# Mynd_Baffle.net
KiCad netlist of a schematic drawn in Altium Designer
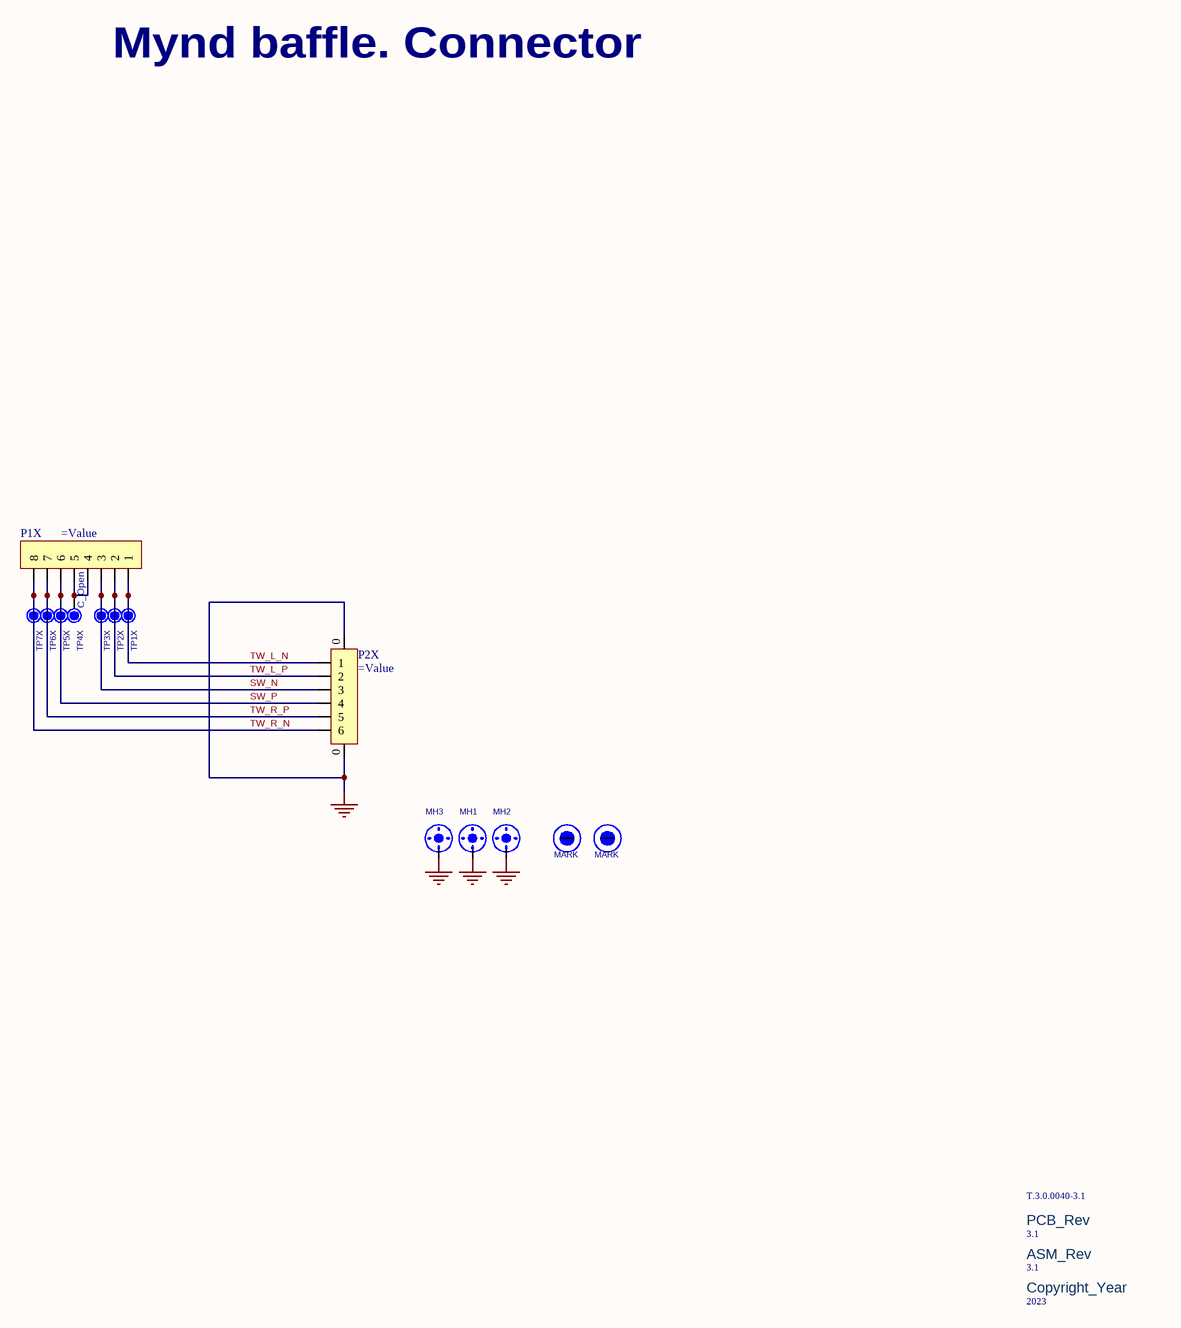
[diagram p0: Mynd_Baffle.SchDoc]

(export (version "E")
  (design (tool "Eeschema 10.0.6"))
  (components
    (comp (ref "MH1")
      (value "SCREW_HOLE_D35")
      (footprint "SCREW_D35")
      (description "SCREW_HOLE D3.5mm")
      (libsource (lib "altium-import") (part "root_1_SCREW_HOLE_"))
    )
    (comp (ref "MH2")
      (value "HOLD_D35")
      (footprint "HOLD_D35")
      (libsource (lib "altium-import") (part "root_1_SCREW_HOLE_"))
    )
    (comp (ref "MH3")
      (value "SCREW_HOLE_D35")
      (footprint "SCREW_D35")
      (description "SCREW_HOLE D3.5mm")
      (libsource (lib "altium-import") (part "root_1_SCREW_HOLE_"))
    )
    (comp (ref "MK1X")
      (value "MARK")
      (footprint "MARK")
      (description "MARK DOT")
      (libsource (lib "altium-import") (part "root_0_MARK_"))
    )
    (comp (ref "MK2X")
      (value "MARK")
      (footprint "MARK")
      (description "MARK DOT")
      (libsource (lib "altium-import") (part "root_0_MARK_"))
    )
    (comp (ref "P1X")
      (value "~")
      (footprint "TSB1_05282")
      (description "SMD BTB CONNECTOR 8P P2.5mm GOLD")
      (fields (field (name "MANUFACTURER") "Generic") (field (name "PART_NUMBER") "8P PITCH=2.5mm"))
      (libsource (lib "altium-import") (part "root_3_CON 8P_"))
    )
    (comp (ref "P2X")
      (value "~")
      (footprint "CON_250_SMD_V_6P")
      (description "GS SMD WTB CONNECTOR 6P P2.5mm")
      (fields (field (name "MANUFACTURER") "Generic") (field (name "PART_NUMBER") "6P PITCH=2.5mm"))
      (libsource (lib "altium-import") (part "root_0_mirrored_CON 6P_F_"))
    )
    (comp (ref "Teufel_ASM_Label1X")
      (value "3.1")
      (footprint "Teufel_ASM_Rev")
      (description "Teufel_ASM_Rev")
      (libsource (lib "altium-import") (part "root_0_Teufel_ASM_Label_"))
    )
    (comp (ref "Teufel_Copyright1X")
      (value "2023")
      (footprint "TEUFEL_COPYRIGHT")
      (description "Teufel_Copyright_Year")
      (libsource (lib "altium-import") (part "root_0_Teufel_Copyright_"))
    )
    (comp (ref "Teufel_PCB_Label1X")
      (value "3.1")
      (footprint "Teufel_PCB_Rev")
      (description "Teufel_PCB_Label")
      (libsource (lib "altium-import") (part "root_0_Teufel_PCB_Label_"))
    )
    (comp (ref "Teufel_PCB_Logo1X")
      (value "-3.1")
      (footprint "Teufel_NoLogo")
      (description "Teufel PCB NoLogo")
      (libsource (lib "altium-import") (part "root_0_Teufel NoLogo_"))
    )
    (comp (ref "TP1X")
      (value "TP12")
      (footprint "TP120")
      (description "Test Point")
      (libsource (lib "altium-import") (part "root_3_TP_"))
    )
    (comp (ref "TP2X")
      (value "TP12")
      (footprint "TP120")
      (description "Test Point")
      (libsource (lib "altium-import") (part "root_3_TP_"))
    )
    (comp (ref "TP3X")
      (value "TP12")
      (footprint "TP120")
      (description "Test Point")
      (libsource (lib "altium-import") (part "root_3_TP_"))
    )
    (comp (ref "TP4X")
      (value "TP12")
      (footprint "TP120")
      (description "Test Point")
      (libsource (lib "altium-import") (part "root_3_TP_"))
    )
    (comp (ref "TP5X")
      (value "TP12")
      (footprint "TP120")
      (description "Test Point")
      (libsource (lib "altium-import") (part "root_3_TP_"))
    )
    (comp (ref "TP6X")
      (value "TP12")
      (footprint "TP120")
      (description "Test Point")
      (libsource (lib "altium-import") (part "root_3_TP_"))
    )
    (comp (ref "TP7X")
      (value "TP12")
      (footprint "TP120")
      (description "Test Point")
      (libsource (lib "altium-import") (part "root_3_TP_"))
    )
  )
  (nets
    (net (code "1") (name "/SW_N") (class "Default")
      (node (ref "P1X") (pin "3") (pinfunction "3_3") (pintype "passive"))
      (node (ref "P2X") (pin "3") (pinfunction "3_3") (pintype "passive"))
      (node (ref "TP3X") (pin "1") (pinfunction "1_1") (pintype "passive"))
    )
    (net (code "2") (name "/SW_P") (class "Default")
      (node (ref "P1X") (pin "6") (pinfunction "6_6") (pintype "passive"))
      (node (ref "P2X") (pin "4") (pinfunction "4_4") (pintype "passive"))
      (node (ref "TP5X") (pin "1") (pinfunction "1_1") (pintype "passive"))
    )
    (net (code "3") (name "/TW_L_N") (class "Default")
      (node (ref "P1X") (pin "1") (pinfunction "1_1") (pintype "passive"))
      (node (ref "P2X") (pin "1") (pinfunction "1_1") (pintype "passive"))
      (node (ref "TP1X") (pin "1") (pinfunction "1_1") (pintype "passive"))
    )
    (net (code "4") (name "/TW_L_P") (class "Default")
      (node (ref "P1X") (pin "2") (pinfunction "2_2") (pintype "passive"))
      (node (ref "P2X") (pin "2") (pinfunction "2_2") (pintype "passive"))
      (node (ref "TP2X") (pin "1") (pinfunction "1_1") (pintype "passive"))
    )
    (net (code "5") (name "/TW_R_N") (class "Default")
      (node (ref "P1X") (pin "8") (pinfunction "8_8") (pintype "passive"))
      (node (ref "P2X") (pin "6") (pinfunction "6_6") (pintype "passive"))
      (node (ref "TP7X") (pin "1") (pinfunction "1_1") (pintype "passive"))
    )
    (net (code "6") (name "/TW_R_P") (class "Default")
      (node (ref "P1X") (pin "7") (pinfunction "7_7") (pintype "passive"))
      (node (ref "P2X") (pin "5") (pinfunction "5_5") (pintype "passive"))
      (node (ref "TP6X") (pin "1") (pinfunction "1_1") (pintype "passive"))
    )
    (net (code "7") (name "GND") (class "Default")
      (node (ref "MH1") (pin "1") (pinfunction "1_1") (pintype "passive"))
      (node (ref "MH2") (pin "1") (pinfunction "1_1") (pintype "passive"))
      (node (ref "MH3") (pin "1") (pinfunction "1_1") (pintype "passive"))
      (node (ref "P2X") (pin "0") (pinfunction "0_0") (pintype "passive"))
    )
    (net (code "8") (name "Net-(P1X-Pad4)") (class "Default")
      (node (ref "P1X") (pin "4") (pinfunction "4_4") (pintype "passive"))
      (node (ref "P1X") (pin "5") (pinfunction "5_5") (pintype "passive"))
      (node (ref "TP4X") (pin "1") (pinfunction "1_1") (pintype "passive"))
    )
    (net (code "9") (name "unconnected-(MK1X-PadMK_B)") (class "Default")
      (node (ref "MK1X") (pin "MK_B") (pinfunction "MK_B_MK_B") (pintype "passive"))
    )
    (net (code "10") (name "unconnected-(MK1X-PadMK_T)") (class "Default")
      (node (ref "MK1X") (pin "MK_T") (pinfunction "MK_T_MK_T") (pintype "passive"))
    )
    (net (code "11") (name "unconnected-(MK2X-PadMK_B)") (class "Default")
      (node (ref "MK2X") (pin "MK_B") (pinfunction "MK_B_MK_B") (pintype "passive"))
    )
    (net (code "12") (name "unconnected-(MK2X-PadMK_T)") (class "Default")
      (node (ref "MK2X") (pin "MK_T") (pinfunction "MK_T_MK_T") (pintype "passive"))
    )
  )
)
